# Pmic.net
KiCad netlist of a schematic drawn in Altium Designer
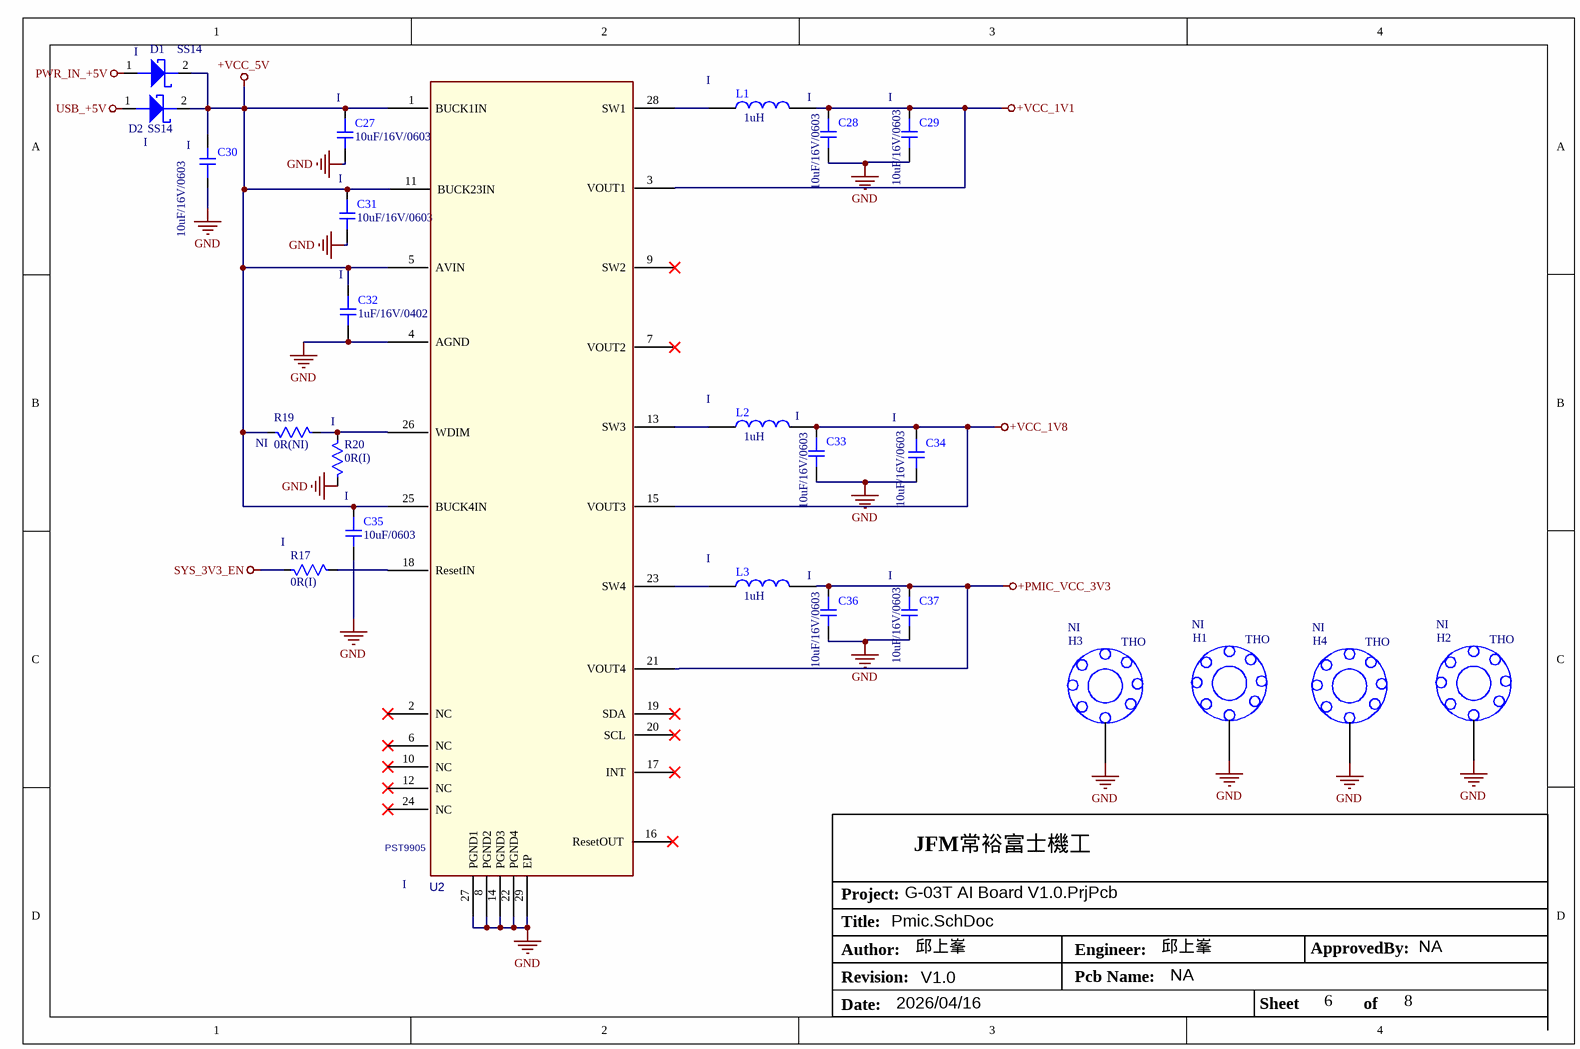
[diagram p0: Pmic.SchDoc]

(export (version "E")
  (design (tool "Eeschema 10.0.6"))
  (components
    (comp (ref "C27")
      (value "10uF/16V/0603")
      (footprint "C0603")
      (fields (field (name "BOM") "I"))
      (libsource (lib "AMIDA7") (part "Cap"))
    )
    (comp (ref "C28")
      (value "10uF/16V/0603")
      (footprint "C0603")
      (fields (field (name "BOM") "I"))
      (libsource (lib "AMIDA7") (part "Cap"))
    )
    (comp (ref "C29")
      (value "10uF/16V/0603")
      (footprint "C0603")
      (fields (field (name "BOM") "I"))
      (libsource (lib "AMIDA7") (part "Cap"))
    )
    (comp (ref "C30")
      (value "10uF/16V/0603")
      (footprint "C0603")
      (fields (field (name "BOM") "I"))
      (libsource (lib "AMIDA7") (part "Cap"))
    )
    (comp (ref "C31")
      (value "10uF/16V/0603")
      (footprint "C0603")
      (fields (field (name "BOM") "I"))
      (libsource (lib "AMIDA7") (part "Cap"))
    )
    (comp (ref "C32")
      (value "1uF/16V/0402")
      (footprint "C0402")
      (fields (field (name "BOM") "I"))
      (libsource (lib "AMIDA7") (part "Cap"))
    )
    (comp (ref "C33")
      (value "10uF/16V/0603")
      (footprint "C0603")
      (fields (field (name "BOM") "I"))
      (libsource (lib "AMIDA7") (part "Cap"))
    )
    (comp (ref "C34")
      (value "10uF/16V/0603")
      (footprint "C0603")
      (fields (field (name "BOM") "I"))
      (libsource (lib "AMIDA7") (part "Cap"))
    )
    (comp (ref "C35")
      (value "10uF/0603")
      (footprint "C0603")
      (fields (field (name "BOM") "I"))
      (libsource (lib "AMIDA7") (part "Cap"))
    )
    (comp (ref "C36")
      (value "10uF/16V/0603")
      (footprint "C0603")
      (fields (field (name "BOM") "I"))
      (libsource (lib "AMIDA7") (part "Cap"))
    )
    (comp (ref "C37")
      (value "10uF/16V/0603")
      (footprint "C0603")
      (fields (field (name "BOM") "I"))
      (libsource (lib "AMIDA7") (part "Cap"))
    )
    (comp (ref "D1")
      (value "SS14")
      (footprint "DO-214AC (SMA)")
      (description "Schottky Diodes & Rectifiers 1A, 40V, Schottky Rectifier")
      (fields (field (name "BOM") "I"))
      (libsource (lib "AMIDA7") (part "DIODE SCHOTTKY"))
    )
    (comp (ref "D2")
      (value "SS14")
      (footprint "DO-214AC (SMA)")
      (description "Schottky Diodes & Rectifiers 1A, 40V, Schottky Rectifier")
      (fields (field (name "BOM") "I"))
      (libsource (lib "AMIDA7") (part "DIODE SCHOTTKY"))
    )
    (comp (ref "H1")
      (value "THO")
      (footprint "TPH-3.4mm")
      (fields (field (name "BOM") "NI"))
      (libsource (lib "AMIDA7") (part "THO"))
    )
    (comp (ref "H2")
      (value "THO")
      (footprint "TPH-3.4mm")
      (fields (field (name "BOM") "NI"))
      (libsource (lib "AMIDA7") (part "THO"))
    )
    (comp (ref "H3")
      (value "THO")
      (footprint "TPH-3.4mm")
      (fields (field (name "BOM") "NI"))
      (libsource (lib "AMIDA7") (part "THO"))
    )
    (comp (ref "H4")
      (value "THO")
      (footprint "TPH-3.4mm")
      (fields (field (name "BOM") "NI"))
      (libsource (lib "AMIDA7") (part "THO"))
    )
    (comp (ref "L1")
      (value "1uH")
      (footprint "INDC2016X100N")
      (description "L")
      (fields (field (name "BOM") "I") (field (name "PUBLISHER") "Altium Limited"))
      (libsource (lib "AMIDA7") (part "L"))
    )
    (comp (ref "L2")
      (value "1uH")
      (footprint "INDC2016X100N")
      (description "L")
      (fields (field (name "BOM") "I") (field (name "PUBLISHER") "Altium Limited"))
      (libsource (lib "AMIDA7") (part "L"))
    )
    (comp (ref "L3")
      (value "1uH")
      (footprint "INDC2016X100N")
      (description "L")
      (fields (field (name "BOM") "I") (field (name "PUBLISHER") "Altium Limited"))
      (libsource (lib "AMIDA7") (part "L"))
    )
    (comp (ref "R17")
      (value "0R(I)")
      (footprint "R0402")
      (description "opt 0R")
      (fields (field (name "BOM") "I"))
      (libsource (lib "AMIDA7") (part "Res"))
    )
    (comp (ref "R19")
      (value "0R(NI)")
      (footprint "R0402")
      (fields (field (name "BOM") "NI"))
      (libsource (lib "AMIDA7") (part "Res"))
    )
    (comp (ref "R20")
      (value "0R(I)")
      (footprint "R0402")
      (description "opt 0R")
      (fields (field (name "BOM") "I"))
      (libsource (lib "AMIDA7") (part "Res"))
    )
    (comp (ref "U2")
      (value "PST9905")
      (footprint "QFN 5X5 28PIN")
      (description "4-Channel Power Management IC for Automotive System")
      (fields (field (name "BOM") "I"))
      (libsource (lib "AMIDA7") (part "PST9905"))
    )
  )
  (nets
    (net (code "1") (name "+PMIC_VCC_3V3") (class "Default")
      (node (ref "C36") (pin "1") (pinfunction "1_1") (pintype "passive"))
      (node (ref "C37") (pin "1") (pinfunction "1_1") (pintype "passive"))
      (node (ref "L3") (pin "2") (pinfunction "2_2") (pintype "passive"))
      (node (ref "U2") (pin "21") (pinfunction "VOUT4_21") (pintype "passive"))
    )
    (net (code "2") (name "+VCC_1V1") (class "Default")
      (node (ref "C28") (pin "1") (pinfunction "1_1") (pintype "passive"))
      (node (ref "C29") (pin "1") (pinfunction "1_1") (pintype "passive"))
      (node (ref "L1") (pin "2") (pinfunction "2_2") (pintype "passive"))
      (node (ref "U2") (pin "3") (pinfunction "VOUT1_3") (pintype "passive"))
    )
    (net (code "3") (name "+VCC_1V8") (class "Default")
      (node (ref "C33") (pin "1") (pinfunction "1_1") (pintype "passive"))
      (node (ref "C34") (pin "1") (pinfunction "1_1") (pintype "passive"))
      (node (ref "L2") (pin "2") (pinfunction "2_2") (pintype "passive"))
      (node (ref "U2") (pin "15") (pinfunction "VOUT3_15") (pintype "passive"))
    )
    (net (code "4") (name "+VCC_5V") (class "Default")
      (node (ref "C27") (pin "1") (pinfunction "1_1") (pintype "passive"))
      (node (ref "C30") (pin "2") (pinfunction "2_2") (pintype "passive"))
      (node (ref "C31") (pin "1") (pinfunction "1_1") (pintype "passive"))
      (node (ref "C32") (pin "1") (pinfunction "1_1") (pintype "passive"))
      (node (ref "C35") (pin "1") (pinfunction "1_1") (pintype "passive"))
      (node (ref "D1") (pin "2") (pinfunction "CATHODE_2") (pintype "passive"))
      (node (ref "D2") (pin "2") (pinfunction "CATHODE_2") (pintype "passive"))
      (node (ref "R19") (pin "2") (pinfunction "2_2") (pintype "passive"))
      (node (ref "U2") (pin "1") (pinfunction "BUCK1IN_1") (pintype "passive"))
      (node (ref "U2") (pin "11") (pinfunction "BUCK23IN_11") (pintype "passive"))
      (node (ref "U2") (pin "25") (pinfunction "BUCK4IN_25") (pintype "passive"))
      (node (ref "U2") (pin "5") (pinfunction "AVIN_5") (pintype "passive"))
    )
    (net (code "5") (name "GND") (class "Default")
      (node (ref "C27") (pin "2") (pinfunction "2_2") (pintype "passive"))
      (node (ref "C28") (pin "2") (pinfunction "2_2") (pintype "passive"))
      (node (ref "C29") (pin "2") (pinfunction "2_2") (pintype "passive"))
      (node (ref "C30") (pin "1") (pinfunction "1_1") (pintype "passive"))
      (node (ref "C31") (pin "2") (pinfunction "2_2") (pintype "passive"))
      (node (ref "C32") (pin "2") (pinfunction "2_2") (pintype "passive"))
      (node (ref "C33") (pin "2") (pinfunction "2_2") (pintype "passive"))
      (node (ref "C34") (pin "2") (pinfunction "2_2") (pintype "passive"))
      (node (ref "C35") (pin "2") (pinfunction "2_2") (pintype "passive"))
      (node (ref "C36") (pin "2") (pinfunction "2_2") (pintype "passive"))
      (node (ref "C37") (pin "2") (pinfunction "2_2") (pintype "passive"))
      (node (ref "H1") (pin "0") (pinfunction "0_0") (pintype "passive"))
      (node (ref "H2") (pin "0") (pinfunction "0_0") (pintype "passive"))
      (node (ref "H3") (pin "0") (pinfunction "0_0") (pintype "passive"))
      (node (ref "H4") (pin "0") (pinfunction "0_0") (pintype "passive"))
      (node (ref "R20") (pin "1") (pinfunction "1_1") (pintype "passive"))
      (node (ref "U2") (pin "14") (pinfunction "PGND3_14") (pintype "passive"))
      (node (ref "U2") (pin "22") (pinfunction "PGND4_22") (pintype "passive"))
      (node (ref "U2") (pin "27") (pinfunction "PGND1_27") (pintype "passive"))
      (node (ref "U2") (pin "29") (pinfunction "EP_29") (pintype "passive"))
      (node (ref "U2") (pin "4") (pinfunction "AGND_4") (pintype "passive"))
      (node (ref "U2") (pin "8") (pinfunction "PGND2_8") (pintype "passive"))
    )
    (net (code "6") (name "Net-(U2-ResetIN)") (class "Default")
      (node (ref "R17") (pin "1") (pinfunction "1_1") (pintype "passive"))
      (node (ref "U2") (pin "18") (pinfunction "ResetIN_18") (pintype "passive"))
    )
    (net (code "7") (name "Net-(U2-SW1)") (class "Default")
      (node (ref "L1") (pin "1") (pinfunction "1_1") (pintype "passive"))
      (node (ref "U2") (pin "28") (pinfunction "SW1_28") (pintype "passive"))
    )
    (net (code "8") (name "Net-(U2-SW3)") (class "Default")
      (node (ref "L2") (pin "1") (pinfunction "1_1") (pintype "passive"))
      (node (ref "U2") (pin "13") (pinfunction "SW3_13") (pintype "passive"))
    )
    (net (code "9") (name "Net-(U2-SW4)") (class "Default")
      (node (ref "L3") (pin "1") (pinfunction "1_1") (pintype "passive"))
      (node (ref "U2") (pin "23") (pinfunction "SW4_23") (pintype "passive"))
    )
    (net (code "10") (name "Net-(U2-WDIM)") (class "Default")
      (node (ref "R19") (pin "1") (pinfunction "1_1") (pintype "passive"))
      (node (ref "R20") (pin "2") (pinfunction "2_2") (pintype "passive"))
      (node (ref "U2") (pin "26") (pinfunction "WDIM_26") (pintype "passive"))
    )
    (net (code "11") (name "PWR_IN_+5V") (class "Default")
      (node (ref "D1") (pin "1") (pinfunction "ANODE_1") (pintype "passive"))
    )
    (net (code "12") (name "SYS_3V3_EN") (class "Default")
      (node (ref "R17") (pin "2") (pinfunction "2_2") (pintype "passive"))
    )
    (net (code "13") (name "USB_+5V") (class "Default")
      (node (ref "D2") (pin "1") (pinfunction "ANODE_1") (pintype "passive"))
    )
    (net (code "14") (name "unconnected-(U2-INT-Pad17)") (class "Default")
      (node (ref "U2") (pin "17") (pinfunction "INT_17") (pintype "passive+no_connect"))
    )
    (net (code "15") (name "unconnected-(U2-NC-Pad2)") (class "Default")
      (node (ref "U2") (pin "2") (pinfunction "NC_2") (pintype "passive"))
    )
    (net (code "16") (name "unconnected-(U2-NC-Pad6)") (class "Default")
      (node (ref "U2") (pin "6") (pinfunction "NC_6") (pintype "passive"))
    )
    (net (code "17") (name "unconnected-(U2-NC-Pad10)") (class "Default")
      (node (ref "U2") (pin "10") (pinfunction "NC_10") (pintype "passive"))
    )
    (net (code "18") (name "unconnected-(U2-NC-Pad12)") (class "Default")
      (node (ref "U2") (pin "12") (pinfunction "NC_12") (pintype "passive"))
    )
    (net (code "19") (name "unconnected-(U2-NC-Pad24)") (class "Default")
      (node (ref "U2") (pin "24") (pinfunction "NC_24") (pintype "passive"))
    )
    (net (code "20") (name "unconnected-(U2-ResetOUT-Pad16)") (class "Default")
      (node (ref "U2") (pin "16") (pinfunction "ResetOUT_16") (pintype "passive+no_connect"))
    )
    (net (code "21") (name "unconnected-(U2-SCL-Pad20)") (class "Default")
      (node (ref "U2") (pin "20") (pinfunction "SCL_20") (pintype "passive+no_connect"))
    )
    (net (code "22") (name "unconnected-(U2-SDA-Pad19)") (class "Default")
      (node (ref "U2") (pin "19") (pinfunction "SDA_19") (pintype "passive+no_connect"))
    )
    (net (code "23") (name "unconnected-(U2-SW2-Pad9)") (class "Default")
      (node (ref "U2") (pin "9") (pinfunction "SW2_9") (pintype "passive+no_connect"))
    )
    (net (code "24") (name "unconnected-(U2-VOUT2-Pad7)") (class "Default")
      (node (ref "U2") (pin "7") (pinfunction "VOUT2_7") (pintype "passive+no_connect"))
    )
  )
)
